# Encoder_Fin_ARM_-_MCU_KL05_24VQFN.net
KiCad netlist of a schematic drawn in Altium Designer
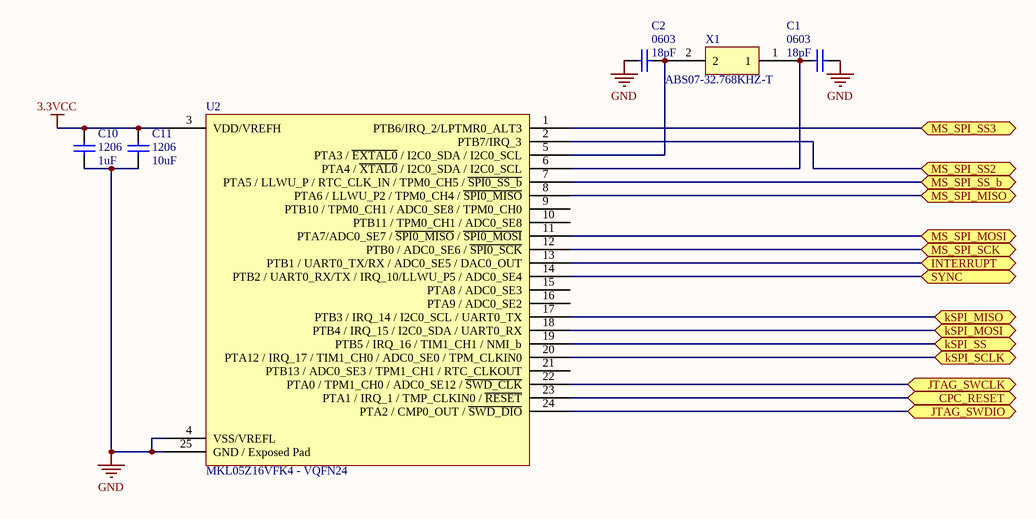
[diagram p0: Encoder Fin ARM - MCU KL05 24VQFN.SchDoc]

(export (version "E")
  (design (tool "Eeschema 10.0.6"))
  (components
    (comp (ref "C1")
      (value "0603")
      (footprint "1608[0603]")
      (description "Capacitor (Semiconductor SIM Model)")
      (fields (field (name "ALTIUM_VALUE") "18pF") (field (name "PUBLISHER") "Altium Limited"))
      (libsource (lib "Miscellaneous Devices") (part "Cap Semi"))
    )
    (comp (ref "C2")
      (value "0603")
      (footprint "1608[0603]")
      (description "Capacitor (Semiconductor SIM Model)")
      (fields (field (name "ALTIUM_VALUE") "18pF") (field (name "PUBLISHER") "Altium Limited"))
      (libsource (lib "Miscellaneous Devices") (part "Cap Semi"))
    )
    (comp (ref "C10")
      (value "1206")
      (footprint "C1206")
      (description "Capacitor (Semiconductor SIM Model)")
      (fields (field (name "ALTIUM_VALUE") "1uF") (field (name "PUBLISHER") "Altium Limited"))
      (libsource (lib "Miscellaneous Devices") (part "Cap Semi"))
    )
    (comp (ref "C11")
      (value "1206")
      (footprint "C1206")
      (description "Capacitor (Semiconductor SIM Model)")
      (fields (field (name "ALTIUM_VALUE") "10uF") (field (name "PUBLISHER") "Altium Limited"))
      (libsource (lib "Miscellaneous Devices") (part "Cap Semi"))
    )
    (comp (ref "U2")
      (value "MKL05Z16VFK4 - VQFN24")
      (footprint "98ASA00474D")
      (description "ARM Cortex M0+")
      (libsource (lib "Encoder Fin") (part "MKL05Z16VFK4 - 24 Pin VQFN"))
    )
    (comp (ref "X1")
      (value "ABS07-32.768KHZ-T")
      (footprint "ABS07-32.768KHZ-T")
      (description "ABS07-32.768KHZ-T RTC Crystal Oscillator")
      (libsource (lib "Adams Altium Library") (part "ABS07-32.768KHZ-T"))
    )
  )
  (nets
    (net (code "1") (name "/CPC_RESET") (class "Default")
      (node (ref "U2") (pin "23") (pinfunction "PTA1_/_IRQ_1_/_TMP_CLKIN0_/_~{RESET}_23") (pintype "passive"))
    )
    (net (code "2") (name "/INTERRUPT") (class "Default")
      (node (ref "U2") (pin "13") (pinfunction "PTB1_/_UART0_TX/RX_/_ADC0_SE5_/_DAC0_OUT_13") (pintype "passive"))
    )
    (net (code "3") (name "/JTAG_SWCLK") (class "Default")
      (node (ref "U2") (pin "22") (pinfunction "PTA0_/_TPM1_CH0_/_ADC0_SE12_/_~{SWD_CLK}_22") (pintype "passive"))
    )
    (net (code "4") (name "/JTAG_SWDIO") (class "Default")
      (node (ref "U2") (pin "24") (pinfunction "PTA2_/_CMP0_OUT_/_~{SWD_DIO}_24") (pintype "passive"))
    )
    (net (code "5") (name "/MS_SPI_MISO") (class "Default")
      (node (ref "U2") (pin "8") (pinfunction "PTA6_/_LLWU_P2_/_TPM0_CH4_/_~{SPI0_MISO}_8") (pintype "passive"))
    )
    (net (code "6") (name "/MS_SPI_MOSI") (class "Default")
      (node (ref "U2") (pin "11") (pinfunction "PTA7/ADC0_SE7_/_~{SPI0_MISO}_/_~{SPI0_MOSI}_11") (pintype "passive"))
    )
    (net (code "7") (name "/MS_SPI_SCK") (class "Default")
      (node (ref "U2") (pin "12") (pinfunction "PTB0_/_ADC0_SE6_/_~{SPI0_SCK}_12") (pintype "passive"))
    )
    (net (code "8") (name "/MS_SPI_SS2") (class "Default")
      (node (ref "U2") (pin "2") (pinfunction "PTB7/IRQ_3_2") (pintype "passive"))
    )
    (net (code "9") (name "/MS_SPI_SS3") (class "Default")
      (node (ref "U2") (pin "1") (pinfunction "PTB6/IRQ_2/LPTMR0_ALT3_1") (pintype "passive"))
    )
    (net (code "10") (name "/MS_SPI_SS_b") (class "Default")
      (node (ref "U2") (pin "7") (pinfunction "PTA5_/_LLWU_P_/_RTC_CLK_IN_/_TPM0_CH5_/_~{SPI0_SS_b}_7") (pintype "passive"))
    )
    (net (code "11") (name "/SYNC") (class "Default")
      (node (ref "U2") (pin "14") (pinfunction "PTB2_/_UART0_RX/TX_/_IRQ_10/LLWU_P5_/_ADC0_SE4_14") (pintype "passive"))
    )
    (net (code "12") (name "/kSPI_MISO") (class "Default")
      (node (ref "U2") (pin "17") (pinfunction "PTB3_/_IRQ_14_/_I2C0_SCL_/_UART0_TX_17") (pintype "passive"))
    )
    (net (code "13") (name "/kSPI_MOSI") (class "Default")
      (node (ref "U2") (pin "18") (pinfunction "PTB4_/_IRQ_15_/_I2C0_SDA_/_UART0_RX_18") (pintype "passive"))
    )
    (net (code "14") (name "/kSPI_SCLK") (class "Default")
      (node (ref "U2") (pin "20") (pinfunction "PTA12_/_IRQ_17_/_TIM1_CH0_/_ADC0_SE0_/_TPM_CLKIN0_20") (pintype "passive"))
    )
    (net (code "15") (name "/kSPI_SS") (class "Default")
      (node (ref "U2") (pin "19") (pinfunction "PTB5_/_IRQ_16_/_TIM1_CH1_/_NMI_b_19") (pintype "passive"))
    )
    (net (code "16") (name "3.3VCC") (class "Default")
      (node (ref "C10") (pin "2") (pinfunction "2_2") (pintype "passive"))
      (node (ref "C11") (pin "2") (pinfunction "2_2") (pintype "passive"))
      (node (ref "U2") (pin "3") (pinfunction "VDD/VREFH_3") (pintype "passive"))
    )
    (net (code "17") (name "GND") (class "Default")
      (node (ref "C1") (pin "2") (pinfunction "2_2") (pintype "passive"))
      (node (ref "C10") (pin "1") (pinfunction "1_1") (pintype "passive"))
      (node (ref "C11") (pin "1") (pinfunction "1_1") (pintype "passive"))
      (node (ref "C2") (pin "2") (pinfunction "2_2") (pintype "passive"))
      (node (ref "U2") (pin "25") (pinfunction "GND_/_Exposed_Pad_25") (pintype "passive"))
      (node (ref "U2") (pin "4") (pinfunction "VSS/VREFL_4") (pintype "passive"))
    )
    (net (code "18") (name "Net-(U2-PTA3_{slash}_~{EXTAL0}_{slash}_I2C0_SDA_{slash}_I2C0_SCL)") (class "Default")
      (node (ref "C2") (pin "1") (pinfunction "1_1") (pintype "passive"))
      (node (ref "U2") (pin "5") (pinfunction "PTA3_/_~{EXTAL0}_/_I2C0_SDA_/_I2C0_SCL_5") (pintype "passive"))
      (node (ref "X1") (pin "2") (pinfunction "2_2") (pintype "passive"))
    )
    (net (code "19") (name "Net-(U2-PTA4_{slash}_~{XTAL0}_{slash}_I2C0_SDA_{slash}_I2C0_SCL)") (class "Default")
      (node (ref "C1") (pin "1") (pinfunction "1_1") (pintype "passive"))
      (node (ref "U2") (pin "6") (pinfunction "PTA4_/_~{XTAL0}_/_I2C0_SDA_/_I2C0_SCL_6") (pintype "passive"))
      (node (ref "X1") (pin "1") (pinfunction "1_1") (pintype "passive"))
    )
    (net (code "20") (name "unconnected-(U2-PTA8_{slash}_ADC0_SE3-Pad15)") (class "Default")
      (node (ref "U2") (pin "15") (pinfunction "PTA8_/_ADC0_SE3_15") (pintype "passive"))
    )
    (net (code "21") (name "unconnected-(U2-PTA9_{slash}_ADC0_SE2-Pad16)") (class "Default")
      (node (ref "U2") (pin "16") (pinfunction "PTA9_/_ADC0_SE2_16") (pintype "passive"))
    )
    (net (code "22") (name "unconnected-(U2-PTB10_{slash}_TPM0_CH1_{slash}_ADC0_SE8_{slash}_TPM0_CH0-Pad9)") (class "Default")
      (node (ref "U2") (pin "9") (pinfunction "PTB10_/_TPM0_CH1_/_ADC0_SE8_/_TPM0_CH0_9") (pintype "passive"))
    )
    (net (code "23") (name "unconnected-(U2-PTB11_{slash}_TPM0_CH1_{slash}_ADC0_SE8-Pad10)") (class "Default")
      (node (ref "U2") (pin "10") (pinfunction "PTB11_/_TPM0_CH1_/_ADC0_SE8_10") (pintype "passive"))
    )
    (net (code "24") (name "unconnected-(U2-PTB13_{slash}_ADC0_SE3_{slash}_TPM1_CH1_{slash}_RTC_CLKOUT-Pad21)") (class "Default")
      (node (ref "U2") (pin "21") (pinfunction "PTB13_/_ADC0_SE3_/_TPM1_CH1_/_RTC_CLKOUT_21") (pintype "passive"))
    )
  )
)
